# bday_cake.net
KiCad netlist of a schematic drawn in EAGLE
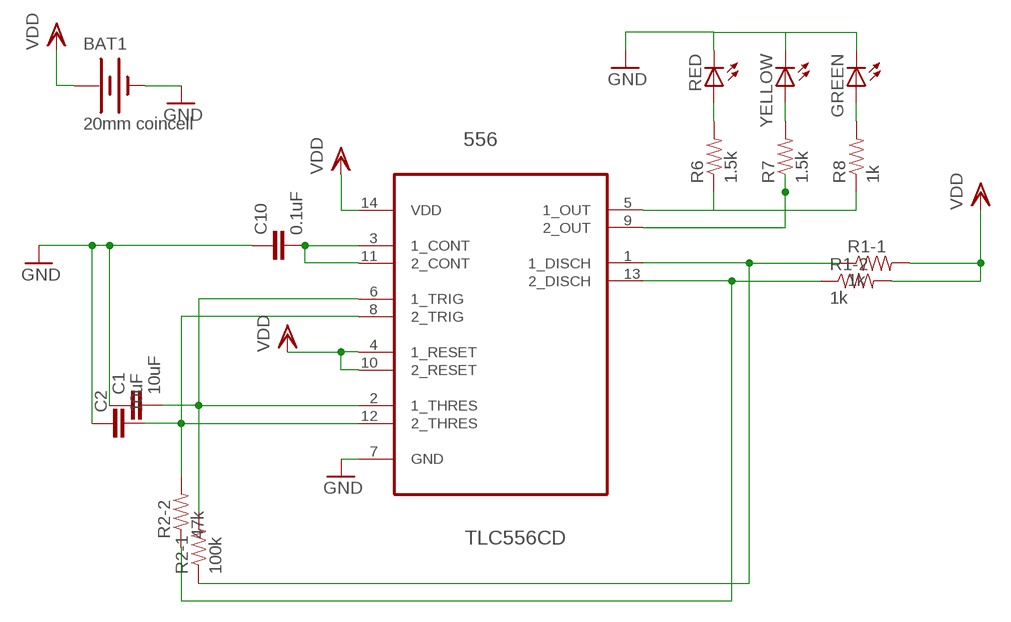
[diagram p0: schematic, sheet 1]

(export (version "E")
  (design (tool "Eeschema 10.0.6"))
  (components
    (comp (ref "556")
      (value "TLC556CD")
      (footprint "eagle-import:SOIC127P600X175-14N")
      (libsource (lib "eagle-import") (part "TLC556CD"))
    )
    (comp (ref "BAT1")
      (value "20mm coincell")
      (footprint "eagle-import:CR2032_HOLDER")
      (libsource (lib "eagle-import") (part "CR2032_HOLDER"))
    )
    (comp (ref "C1")
      (value "10uF")
      (footprint "eagle-import:0805")
      (libsource (lib "eagle-import") (part "CAP0805"))
    )
    (comp (ref "C2")
      (value "10uF")
      (footprint "eagle-import:0805")
      (libsource (lib "eagle-import") (part "CAP0805"))
    )
    (comp (ref "C10")
      (value "0.1uF")
      (footprint "eagle-import:0805")
      (libsource (lib "eagle-import") (part "CAP0805"))
    )
    (comp (ref "GREEN")
      (value "LEDSMT1206")
      (footprint "eagle-import:1206")
      (libsource (lib "eagle-import") (part "LEDSMT1206"))
    )
    (comp (ref "R1-1")
      (value "1k")
      (footprint "eagle-import:0805")
      (libsource (lib "eagle-import") (part "RESISTOR0805-RES"))
    )
    (comp (ref "R1-2")
      (value "1k")
      (footprint "eagle-import:0805")
      (libsource (lib "eagle-import") (part "RESISTOR0805-RES"))
    )
    (comp (ref "R2-1")
      (value "100k")
      (footprint "eagle-import:0805")
      (libsource (lib "eagle-import") (part "RESISTOR0805-RES"))
    )
    (comp (ref "R2-2")
      (value "47k")
      (footprint "eagle-import:0805")
      (libsource (lib "eagle-import") (part "RESISTOR0805-RES"))
    )
    (comp (ref "R6")
      (value "1.5k")
      (footprint "eagle-import:0805")
      (libsource (lib "eagle-import") (part "RESISTOR0805-RES"))
    )
    (comp (ref "R7")
      (value "1.5k")
      (footprint "eagle-import:0805")
      (libsource (lib "eagle-import") (part "RESISTOR0805-RES"))
    )
    (comp (ref "R8")
      (value "1k")
      (footprint "eagle-import:0805")
      (libsource (lib "eagle-import") (part "RESISTOR0805-RES"))
    )
    (comp (ref "RED")
      (value "LEDSMT1206")
      (footprint "eagle-import:1206")
      (libsource (lib "eagle-import") (part "LEDSMT1206"))
    )
    (comp (ref "YELLOW")
      (value "LEDSMT1206")
      (footprint "eagle-import:1206")
      (libsource (lib "eagle-import") (part "LEDSMT1206"))
    )
  )
  (nets
    (net (code "1") (name "GND") (class "Default")
      (node (ref "556") (pin "7") (pinfunction "GND_7") (pintype "passive"))
      (node (ref "BAT1") (pin "CENTER") (pinfunction "-_CENTER") (pintype "power_in"))
      (node (ref "C1") (pin "1") (pinfunction "1_1") (pintype "passive"))
      (node (ref "C10") (pin "1") (pinfunction "1_1") (pintype "passive"))
      (node (ref "C2") (pin "1") (pinfunction "1_1") (pintype "passive"))
      (node (ref "GREEN") (pin "C") (pinfunction "C_C") (pintype "passive"))
      (node (ref "RED") (pin "C") (pinfunction "C_C") (pintype "passive"))
      (node (ref "YELLOW") (pin "C") (pinfunction "C_C") (pintype "passive"))
    )
    (net (code "2") (name "Net-(556-1_CONT)") (class "Default")
      (node (ref "556") (pin "11") (pinfunction "2_CONT_11") (pintype "input"))
      (node (ref "556") (pin "3") (pinfunction "1_CONT_3") (pintype "input"))
      (node (ref "C10") (pin "2") (pinfunction "2_2") (pintype "passive"))
    )
    (net (code "3") (name "Net-(556-1_DISCH)") (class "Default")
      (node (ref "556") (pin "1") (pinfunction "1_DISCH_1") (pintype "output"))
      (node (ref "R1-1") (pin "1") (pinfunction "1_1") (pintype "passive"))
      (node (ref "R2-1") (pin "1") (pinfunction "1_1") (pintype "passive"))
    )
    (net (code "4") (name "Net-(556-1_OUT)") (class "Default")
      (node (ref "556") (pin "5") (pinfunction "1_OUT_5") (pintype "output"))
      (node (ref "R6") (pin "1") (pinfunction "1_1") (pintype "passive"))
      (node (ref "R8") (pin "1") (pinfunction "1_1") (pintype "passive"))
    )
    (net (code "5") (name "Net-(556-1_THRES)") (class "Default")
      (node (ref "556") (pin "2") (pinfunction "1_THRES_2") (pintype "input"))
      (node (ref "556") (pin "6") (pinfunction "1_TRIG_6") (pintype "input"))
      (node (ref "C1") (pin "2") (pinfunction "2_2") (pintype "passive"))
      (node (ref "R2-1") (pin "2") (pinfunction "2_2") (pintype "passive"))
    )
    (net (code "6") (name "Net-(556-2_DISCH)") (class "Default")
      (node (ref "556") (pin "13") (pinfunction "2_DISCH_13") (pintype "output"))
      (node (ref "R1-2") (pin "1") (pinfunction "1_1") (pintype "passive"))
      (node (ref "R2-2") (pin "1") (pinfunction "1_1") (pintype "passive"))
    )
    (net (code "7") (name "Net-(556-2_OUT)") (class "Default")
      (node (ref "556") (pin "9") (pinfunction "2_OUT_9") (pintype "output"))
      (node (ref "R7") (pin "1") (pinfunction "1_1") (pintype "passive"))
    )
    (net (code "8") (name "Net-(556-2_THRES)") (class "Default")
      (node (ref "556") (pin "12") (pinfunction "2_THRES_12") (pintype "input"))
      (node (ref "556") (pin "8") (pinfunction "2_TRIG_8") (pintype "input"))
      (node (ref "C2") (pin "2") (pinfunction "2_2") (pintype "passive"))
      (node (ref "R2-2") (pin "2") (pinfunction "2_2") (pintype "passive"))
    )
    (net (code "9") (name "Net-(GREEN-PadA)") (class "Default")
      (node (ref "GREEN") (pin "A") (pinfunction "A_A") (pintype "passive"))
      (node (ref "R8") (pin "2") (pinfunction "2_2") (pintype "passive"))
    )
    (net (code "10") (name "Net-(R6-Pad2)") (class "Default")
      (node (ref "R6") (pin "2") (pinfunction "2_2") (pintype "passive"))
      (node (ref "RED") (pin "A") (pinfunction "A_A") (pintype "passive"))
    )
    (net (code "11") (name "Net-(R7-Pad2)") (class "Default")
      (node (ref "R7") (pin "2") (pinfunction "2_2") (pintype "passive"))
      (node (ref "YELLOW") (pin "A") (pinfunction "A_A") (pintype "passive"))
    )
    (net (code "12") (name "VDD") (class "Default")
      (node (ref "556") (pin "10") (pinfunction "2_RESET_10") (pintype "input"))
      (node (ref "556") (pin "14") (pinfunction "VDD_14") (pintype "power_in"))
      (node (ref "556") (pin "4") (pinfunction "1_RESET_4") (pintype "input"))
      (node (ref "BAT1") (pin "VDD1") (pinfunction "+_VDD1") (pintype "power_in"))
      (node (ref "BAT1") (pin "VDD2") (pinfunction "+_VDD2") (pintype "power_in"))
      (node (ref "R1-1") (pin "2") (pinfunction "2_2") (pintype "passive"))
      (node (ref "R1-2") (pin "2") (pinfunction "2_2") (pintype "passive"))
    )
  )
)
